# RGMII.net
KiCad netlist of a schematic drawn in Altium Designer
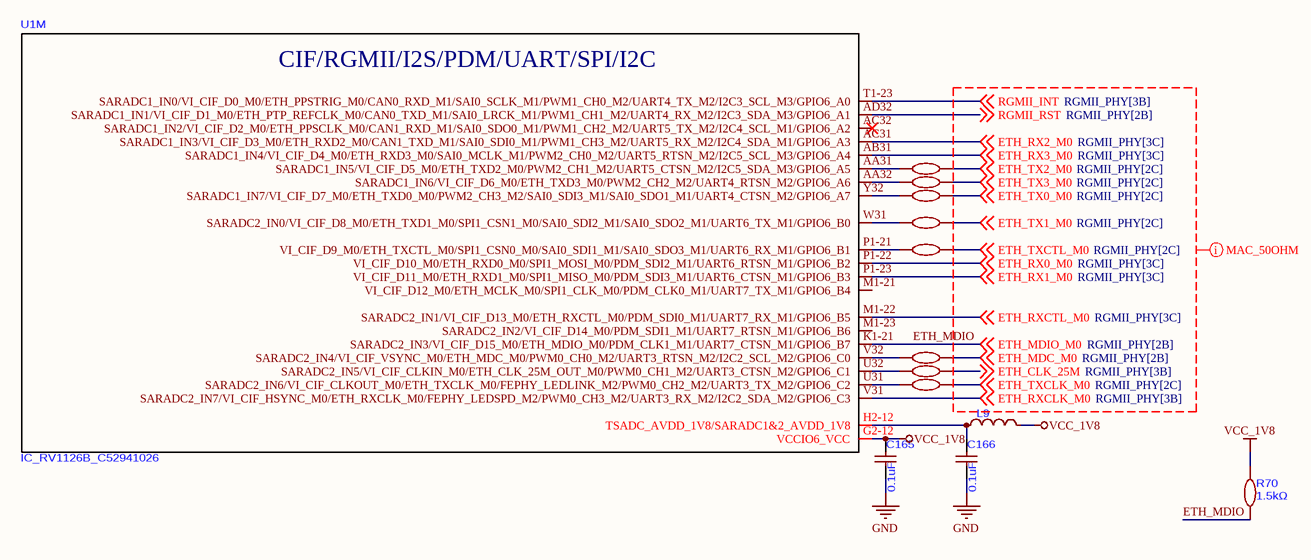
[diagram p0: RGMII.SchDoc]

(export (version "E")
  (design (tool "Eeschema 10.0.6"))
  (components
    (comp (ref "C165")
      (value "0.1uF")
      (footprint "C0201")
      (description "0.1uF ±10% 6.3V Ceramic Capacitor X5R 0201")
      (libsource (lib "Schlib1") (part "CAP_100nF-6.3V-10%-0201_1"))
    )
    (comp (ref "C166")
      (value "0.1uF")
      (footprint "C0201")
      (description "0.1uF ±10% 6.3V Ceramic Capacitor X5R 0201")
      (libsource (lib "Schlib1") (part "CAP_100nF-6.3V-10%-0201_1"))
    )
    (comp (ref "L9")
      (value "FERRITE BEAD 120Ω 0201 1LN")
      (footprint "R0402")
      (description "120 Ohms @ 100MHz 1 Power Line Ferrite Bead 0201 1A 130mOhm")
      (libsource (lib "Schlib1") (part "MPZ0603S121HT000"))
    )
    (comp (ref "R62")
      (value "0Ω")
      (footprint "R0201")
      (description "RES 0Ω ±1% 50mW 0201")
      (libsource (lib "Schlib1") (part "RES_0OHM-50mW-1%-0201"))
    )
    (comp (ref "R63")
      (value "0Ω")
      (footprint "R0201")
      (description "RES 0Ω ±1% 50mW 0201")
      (libsource (lib "Schlib1") (part "RES_0OHM-50mW-1%-0201"))
    )
    (comp (ref "R64")
      (value "0Ω")
      (footprint "R0201")
      (description "RES 0Ω ±1% 50mW 0201")
      (libsource (lib "Schlib1") (part "RES_0OHM-50mW-1%-0201"))
    )
    (comp (ref "R65")
      (value "0Ω")
      (footprint "R0201")
      (description "RES 0Ω ±1% 50mW 0201")
      (libsource (lib "Schlib1") (part "RES_0OHM-50mW-1%-0201"))
    )
    (comp (ref "R66")
      (value "0Ω")
      (footprint "R0201")
      (description "RES 0Ω ±1% 50mW 0201")
      (libsource (lib "Schlib1") (part "RES_0OHM-50mW-1%-0201"))
    )
    (comp (ref "R67")
      (value "0Ω")
      (footprint "R0201")
      (description "RES 0Ω ±1% 50mW 0201")
      (libsource (lib "Schlib1") (part "RES_0OHM-50mW-1%-0201"))
    )
    (comp (ref "R68")
      (value "0Ω")
      (footprint "R0201")
      (description "RES 0Ω ±1% 50mW 0201")
      (libsource (lib "Schlib1") (part "RES_0OHM-50mW-1%-0201"))
    )
    (comp (ref "R69")
      (value "0Ω")
      (footprint "R0201")
      (description "RES 0Ω ±1% 50mW 0201")
      (libsource (lib "Schlib1") (part "RES_0OHM-50mW-1%-0201"))
    )
    (comp (ref "R70")
      (value "1.5kΩ")
      (footprint "R0201")
      (description "RES 1500Ω ±1% 0.05W 0201")
      (libsource (lib "Schlib1") (part "RES_1.5K-0.05W-1%-0201"))
    )
    (comp (ref "U1")
      (value "IC_RV1126B_C52941026")
      (footprint "CCSP-491_L14.0-W14.0-TL_RV1126B")
      (libsource (lib "Schlib1") (part "IC_RV1126B_C52941026"))
    )
  )
  (nets
    (net (code "1") (name "ETH_CLK_25M") (class "Default")
      (node (ref "R68") (pin "2") (pinfunction "2_2") (pintype "passive"))
    )
    (net (code "2") (name "ETH_MDC_M0") (class "Default")
      (node (ref "R67") (pin "2") (pinfunction "2_2") (pintype "passive"))
    )
    (net (code "3") (name "ETH_MDIO_M0") (class "Default")
      (node (ref "R70") (pin "1") (pinfunction "1_1") (pintype "passive"))
      (node (ref "U1") (pin "K1-21") (pinfunction "SARADC2_IN3/VI_CIF_D15_M0/ETH_MDIO_M0/PDM_CLK1_M1/UART7_CTSN_M1/GPIO6_B7_K1-21") (pintype "passive"))
    )
    (net (code "4") (name "ETH_RX0_M0") (class "Default")
      (node (ref "U1") (pin "P1-22") (pinfunction "VI_CIF_D10_M0/ETH_RXD0_M0/SPI1_MOSI_M0/PDM_SDI2_M1/UART6_RTSN_M1/GPIO6_B2_P1-22") (pintype "passive"))
    )
    (net (code "5") (name "ETH_RX1_M0") (class "Default")
      (node (ref "U1") (pin "P1-23") (pinfunction "VI_CIF_D11_M0/ETH_RXD1_M0/SPI1_MISO_M0/PDM_SDI3_M1/UART6_CTSN_M1/GPIO6_B3_P1-23") (pintype "passive"))
    )
    (net (code "6") (name "ETH_RX2_M0") (class "Default")
      (node (ref "U1") (pin "AC31") (pinfunction "SARADC1_IN3/VI_CIF_D3_M0/ETH_RXD2_M0/CAN1_TXD_M1/SAI0_SDI0_M1/PWM1_CH3_M2/UART5_RX_M2/I2C4_SDA_M1/GPIO6_A3_AC31") (pintype "passive"))
    )
    (net (code "7") (name "ETH_RX3_M0") (class "Default")
      (node (ref "U1") (pin "AB31") (pinfunction "SARADC1_IN4/VI_CIF_D4_M0/ETH_RXD3_M0/SAI0_MCLK_M1/PWM2_CH0_M2/UART5_RTSN_M2/I2C5_SCL_M3/GPIO6_A4_AB31") (pintype "passive"))
    )
    (net (code "8") (name "ETH_RXCLK_M0") (class "Default")
      (node (ref "U1") (pin "V31") (pinfunction "SARADC2_IN7/VI_CIF_HSYNC_M0/ETH_RXCLK_M0/FEPHY_LEDSPD_M2/PWM0_CH3_M2/UART3_RX_M2/I2C2_SDA_M2/GPIO6_C3_V31") (pintype "passive"))
    )
    (net (code "9") (name "ETH_RXCTL_M0") (class "Default")
      (node (ref "U1") (pin "M1-22") (pinfunction "SARADC2_IN1/VI_CIF_D13_M0/ETH_RXCTL_M0/PDM_SDI0_M1/UART7_RX_M1/GPIO6_B5_M1-22") (pintype "passive"))
    )
    (net (code "10") (name "ETH_TX0_M0") (class "Default")
      (node (ref "R64") (pin "2") (pinfunction "2_2") (pintype "passive"))
    )
    (net (code "11") (name "ETH_TX1_M0") (class "Default")
      (node (ref "R65") (pin "2") (pinfunction "2_2") (pintype "passive"))
    )
    (net (code "12") (name "ETH_TX2_M0") (class "Default")
      (node (ref "R62") (pin "2") (pinfunction "2_2") (pintype "passive"))
    )
    (net (code "13") (name "ETH_TX3_M0") (class "Default")
      (node (ref "R63") (pin "2") (pinfunction "2_2") (pintype "passive"))
    )
    (net (code "14") (name "ETH_TXCLK_M0") (class "Default")
      (node (ref "R69") (pin "2") (pinfunction "2_2") (pintype "passive"))
    )
    (net (code "15") (name "ETH_TXCTL_M0") (class "Default")
      (node (ref "R66") (pin "2") (pinfunction "2_2") (pintype "passive"))
    )
    (net (code "16") (name "GND") (class "Default")
      (node (ref "C165") (pin "1") (pinfunction "1_1") (pintype "passive"))
      (node (ref "C166") (pin "1") (pinfunction "1_1") (pintype "passive"))
    )
    (net (code "17") (name "Net-(U1M-SARADC1_IN5{slash}VI_CIF_D5_M0{slash}ETH_TXD2_M0{slash}PWM2_CH1_M2{slash}UART5_CTSN_M2{slash}I2C5_SDA_M3{slash}GPIO6_A5)") (class "Default")
      (node (ref "R62") (pin "1") (pinfunction "1_1") (pintype "passive"))
      (node (ref "U1") (pin "AA31") (pinfunction "SARADC1_IN5/VI_CIF_D5_M0/ETH_TXD2_M0/PWM2_CH1_M2/UART5_CTSN_M2/I2C5_SDA_M3/GPIO6_A5_AA31") (pintype "passive"))
    )
    (net (code "18") (name "Net-(U1M-SARADC1_IN6{slash}VI_CIF_D6_M0{slash}ETH_TXD3_M0{slash}PWM2_CH2_M2{slash}UART4_RTSN_M2{slash}GPIO6_A6)") (class "Default")
      (node (ref "R63") (pin "1") (pinfunction "1_1") (pintype "passive"))
      (node (ref "U1") (pin "AA32") (pinfunction "SARADC1_IN6/VI_CIF_D6_M0/ETH_TXD3_M0/PWM2_CH2_M2/UART4_RTSN_M2/GPIO6_A6_AA32") (pintype "passive"))
    )
    (net (code "19") (name "Net-(U1M-SARADC1_IN7{slash}VI_CIF_D7_M0{slash}ETH_TXD0_M0{slash}PWM2_CH3_M2{slash}SAI0_SDI3_M1{slash}SAI0_SDO1_M1{slash}UART4_CTSN_M2{slash}GPIO6_A7)") (class "Default")
      (node (ref "R64") (pin "1") (pinfunction "1_1") (pintype "passive"))
      (node (ref "U1") (pin "Y32") (pinfunction "SARADC1_IN7/VI_CIF_D7_M0/ETH_TXD0_M0/PWM2_CH3_M2/SAI0_SDI3_M1/SAI0_SDO1_M1/UART4_CTSN_M2/GPIO6_A7_Y32") (pintype "passive"))
    )
    (net (code "20") (name "Net-(U1M-SARADC2_IN0{slash}VI_CIF_D8_M0{slash}ETH_TXD1_M0{slash}SPI1_CSN1_M0{slash}SAI0_SDI2_M1{slash}SAI0_SDO2_M1{slash}UART6_TX_M1{slash}GPIO6_B0)") (class "Default")
      (node (ref "R65") (pin "1") (pinfunction "1_1") (pintype "passive"))
      (node (ref "U1") (pin "W31") (pinfunction "SARADC2_IN0/VI_CIF_D8_M0/ETH_TXD1_M0/SPI1_CSN1_M0/SAI0_SDI2_M1/SAI0_SDO2_M1/UART6_TX_M1/GPIO6_B0_W31") (pintype "passive"))
    )
    (net (code "21") (name "Net-(U1M-SARADC2_IN4{slash}VI_CIF_VSYNC_M0{slash}ETH_MDC_M0{slash}PWM0_CH0_M2{slash}UART3_RTSN_M2{slash}I2C2_SCL_M2{slash}GPIO6_C0)") (class "Default")
      (node (ref "R67") (pin "1") (pinfunction "1_1") (pintype "passive"))
      (node (ref "U1") (pin "V32") (pinfunction "SARADC2_IN4/VI_CIF_VSYNC_M0/ETH_MDC_M0/PWM0_CH0_M2/UART3_RTSN_M2/I2C2_SCL_M2/GPIO6_C0_V32") (pintype "passive"))
    )
    (net (code "22") (name "Net-(U1M-SARADC2_IN5{slash}VI_CIF_CLKIN_M0{slash}ETH_CLK_25M_OUT_M0{slash}PWM0_CH1_M2{slash}UART3_CTSN_M2{slash}GPIO6_C1)") (class "Default")
      (node (ref "R68") (pin "1") (pinfunction "1_1") (pintype "passive"))
      (node (ref "U1") (pin "U32") (pinfunction "SARADC2_IN5/VI_CIF_CLKIN_M0/ETH_CLK_25M_OUT_M0/PWM0_CH1_M2/UART3_CTSN_M2/GPIO6_C1_U32") (pintype "passive"))
    )
    (net (code "23") (name "Net-(U1M-SARADC2_IN6{slash}VI_CIF_CLKOUT_M0{slash}ETH_TXCLK_M0{slash}FEPHY_LEDLINK_M2{slash}PWM0_CH2_M2{slash}UART3_TX_M2{slash}GPIO6_C2)") (class "Default")
      (node (ref "R69") (pin "1") (pinfunction "1_1") (pintype "passive"))
      (node (ref "U1") (pin "U31") (pinfunction "SARADC2_IN6/VI_CIF_CLKOUT_M0/ETH_TXCLK_M0/FEPHY_LEDLINK_M2/PWM0_CH2_M2/UART3_TX_M2/GPIO6_C2_U31") (pintype "passive"))
    )
    (net (code "24") (name "Net-(U1M-TSADC_AVDD_1V8{slash}SARADC1&2_AVDD_1V8)") (class "Default")
      (node (ref "C166") (pin "2") (pinfunction "2_2") (pintype "passive"))
      (node (ref "L9") (pin "1") (pinfunction "1_1") (pintype "passive"))
      (node (ref "U1") (pin "H2-12") (pinfunction "TSADC_AVDD_1V8/SARADC1&2_AVDD_1V8_H2-12") (pintype "passive"))
    )
    (net (code "25") (name "Net-(U1M-VI_CIF_D9_M0{slash}ETH_TXCTL_M0{slash}SPI1_CSN0_M0{slash}SAI0_SDI1_M1{slash}SAI0_SDO3_M1{slash}UART6_RX_M1{slash}GPIO6_B1)") (class "Default")
      (node (ref "R66") (pin "1") (pinfunction "1_1") (pintype "passive"))
      (node (ref "U1") (pin "P1-21") (pinfunction "VI_CIF_D9_M0/ETH_TXCTL_M0/SPI1_CSN0_M0/SAI0_SDI1_M1/SAI0_SDO3_M1/UART6_RX_M1/GPIO6_B1_P1-21") (pintype "passive"))
    )
    (net (code "26") (name "RGMII_INT") (class "Default")
      (node (ref "U1") (pin "T1-23") (pinfunction "SARADC1_IN0/VI_CIF_D0_M0/ETH_PPSTRIG_M0/CAN0_RXD_M1/SAI0_SCLK_M1/PWM1_CH0_M2/UART4_TX_M2/I2C3_SCL_M3/GPIO6_A0_T1-23") (pintype "passive"))
    )
    (net (code "27") (name "RGMII_RST") (class "Default")
      (node (ref "U1") (pin "AD32") (pinfunction "SARADC1_IN1/VI_CIF_D1_M0/ETH_PTP_REFCLK_M0/CAN0_TXD_M1/SAI0_LRCK_M1/PWM1_CH1_M2/UART4_RX_M2/I2C3_SDA_M3/GPIO6_A1_AD32") (pintype "passive"))
    )
    (net (code "28") (name "VCC_1V8") (class "Default")
      (node (ref "C165") (pin "2") (pinfunction "2_2") (pintype "passive"))
      (node (ref "L9") (pin "2") (pinfunction "2_2") (pintype "passive"))
      (node (ref "R70") (pin "2") (pinfunction "2_2") (pintype "passive"))
      (node (ref "U1") (pin "G2-12") (pinfunction "VCCIO6_VCC_G2-12") (pintype "passive"))
    )
    (net (code "29") (name "unconnected-(U1M-SARADC1_IN2{slash}VI_CIF_D2_M0{slash}ETH_PPSCLK_M0{slash}CAN1_RXD_M1{slash}SAI0_SDO0_M1{slash}PWM1_CH2_M2{slash}UART5_TX_M2{slash}I2C4_SCL_M1{slash}GPIO6_A2-PadAC32)") (class "Default")
      (node (ref "U1") (pin "AC32") (pinfunction "SARADC1_IN2/VI_CIF_D2_M0/ETH_PPSCLK_M0/CAN1_RXD_M1/SAI0_SDO0_M1/PWM1_CH2_M2/UART5_TX_M2/I2C4_SCL_M1/GPIO6_A2_AC32") (pintype "passive+no_connect"))
    )
    (net (code "30") (name "unconnected-(U1M-SARADC2_IN2{slash}VI_CIF_D14_M0{slash}PDM_SDI1_M1{slash}UART7_RTSN_M1{slash}GPIO6_B6-PadM1-23)") (class "Default")
      (node (ref "U1") (pin "M1-23") (pinfunction "SARADC2_IN2/VI_CIF_D14_M0/PDM_SDI1_M1/UART7_RTSN_M1/GPIO6_B6_M1-23") (pintype "passive"))
    )
    (net (code "31") (name "unconnected-(U1M-VI_CIF_D12_M0{slash}ETH_MCLK_M0{slash}SPI1_CLK_M0{slash}PDM_CLK0_M1{slash}UART7_TX_M1{slash}GPIO6_B4-PadM1-21)") (class "Default")
      (node (ref "U1") (pin "M1-21") (pinfunction "VI_CIF_D12_M0/ETH_MCLK_M0/SPI1_CLK_M0/PDM_CLK0_M1/UART7_TX_M1/GPIO6_B4_M1-21") (pintype "passive"))
    )
  )
)
